# untitled.net
KiCad netlist of a schematic drawn in EAGLE
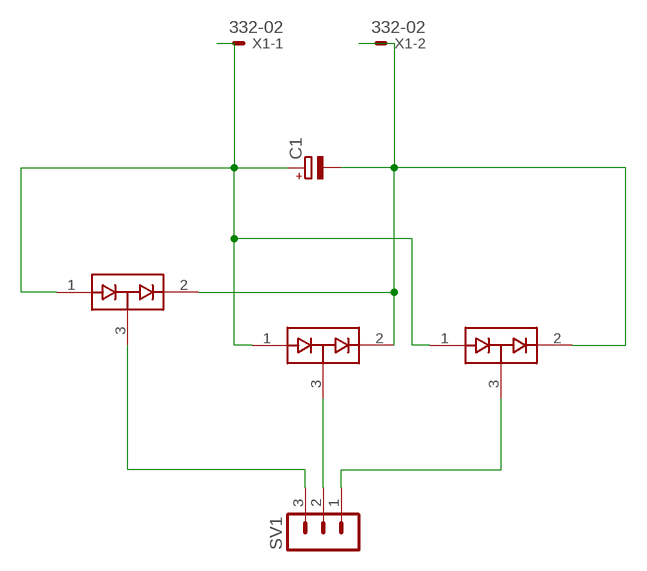
[diagram p0: schematic, sheet 1]

(export (version "E")
  (design (tool "Eeschema 10.0.6"))
  (components
    (comp (ref "C1")
      (value "CPOL-EUE2-5")
      (footprint "eagle-import:E2-5")
      (libsource (lib "eagle-import") (part "CPOL-EUE2-5"))
    )
    (comp (ref "D1")
      (value "BAV99")
      (footprint "eagle-import:SOT23-3")
      (libsource (lib "eagle-import") (part "BAV99"))
    )
    (comp (ref "D2")
      (value "BAV99")
      (footprint "eagle-import:SOT23-3")
      (libsource (lib "eagle-import") (part "BAV99"))
    )
    (comp (ref "D3")
      (value "BAV99")
      (footprint "eagle-import:SOT23-3")
      (libsource (lib "eagle-import") (part "BAV99"))
    )
    (comp (ref "SV1")
      (value "MA03-1")
      (footprint "eagle-import:MA03-1")
      (libsource (lib "eagle-import") (part "MA03-1"))
    )
    (comp (ref "X1")
      (value "332-02")
      (footprint "eagle-import:332-02")
      (libsource (lib "eagle-import") (part "332-02"))
    )
  )
  (nets
    (net (code "1") (name "Net-(D1-A1)") (class "Default")
      (node (ref "C1") (pin "+") (pinfunction "+_+") (pintype "passive"))
      (node (ref "D1") (pin "1") (pinfunction "A1_1") (pintype "bidirectional"))
      (node (ref "D2") (pin "1") (pinfunction "A1_1") (pintype "bidirectional"))
      (node (ref "D3") (pin "1") (pinfunction "A1_1") (pintype "bidirectional"))
      (node (ref "X1") (pin "1") (pinfunction "S_1") (pintype "passive"))
    )
    (net (code "2") (name "Net-(D1-C2)") (class "Default")
      (node (ref "C1") (pin "-") (pinfunction "-_-") (pintype "passive"))
      (node (ref "D1") (pin "2") (pinfunction "C2_2") (pintype "bidirectional"))
      (node (ref "D2") (pin "2") (pinfunction "C2_2") (pintype "bidirectional"))
      (node (ref "D3") (pin "2") (pinfunction "C2_2") (pintype "bidirectional"))
      (node (ref "X1") (pin "2") (pinfunction "S_2") (pintype "passive"))
    )
    (net (code "3") (name "Net-(D1-COM)") (class "Default")
      (node (ref "D1") (pin "3") (pinfunction "COM_3") (pintype "bidirectional"))
      (node (ref "SV1") (pin "3") (pinfunction "3_3") (pintype "passive"))
    )
    (net (code "4") (name "Net-(D2-COM)") (class "Default")
      (node (ref "D2") (pin "3") (pinfunction "COM_3") (pintype "bidirectional"))
      (node (ref "SV1") (pin "2") (pinfunction "2_2") (pintype "passive"))
    )
    (net (code "5") (name "Net-(D3-COM)") (class "Default")
      (node (ref "D3") (pin "3") (pinfunction "COM_3") (pintype "bidirectional"))
      (node (ref "SV1") (pin "1") (pinfunction "1_1") (pintype "passive"))
    )
  )
)
